# signal_proccessing.net
KiCad netlist of a schematic drawn in Altium Designer
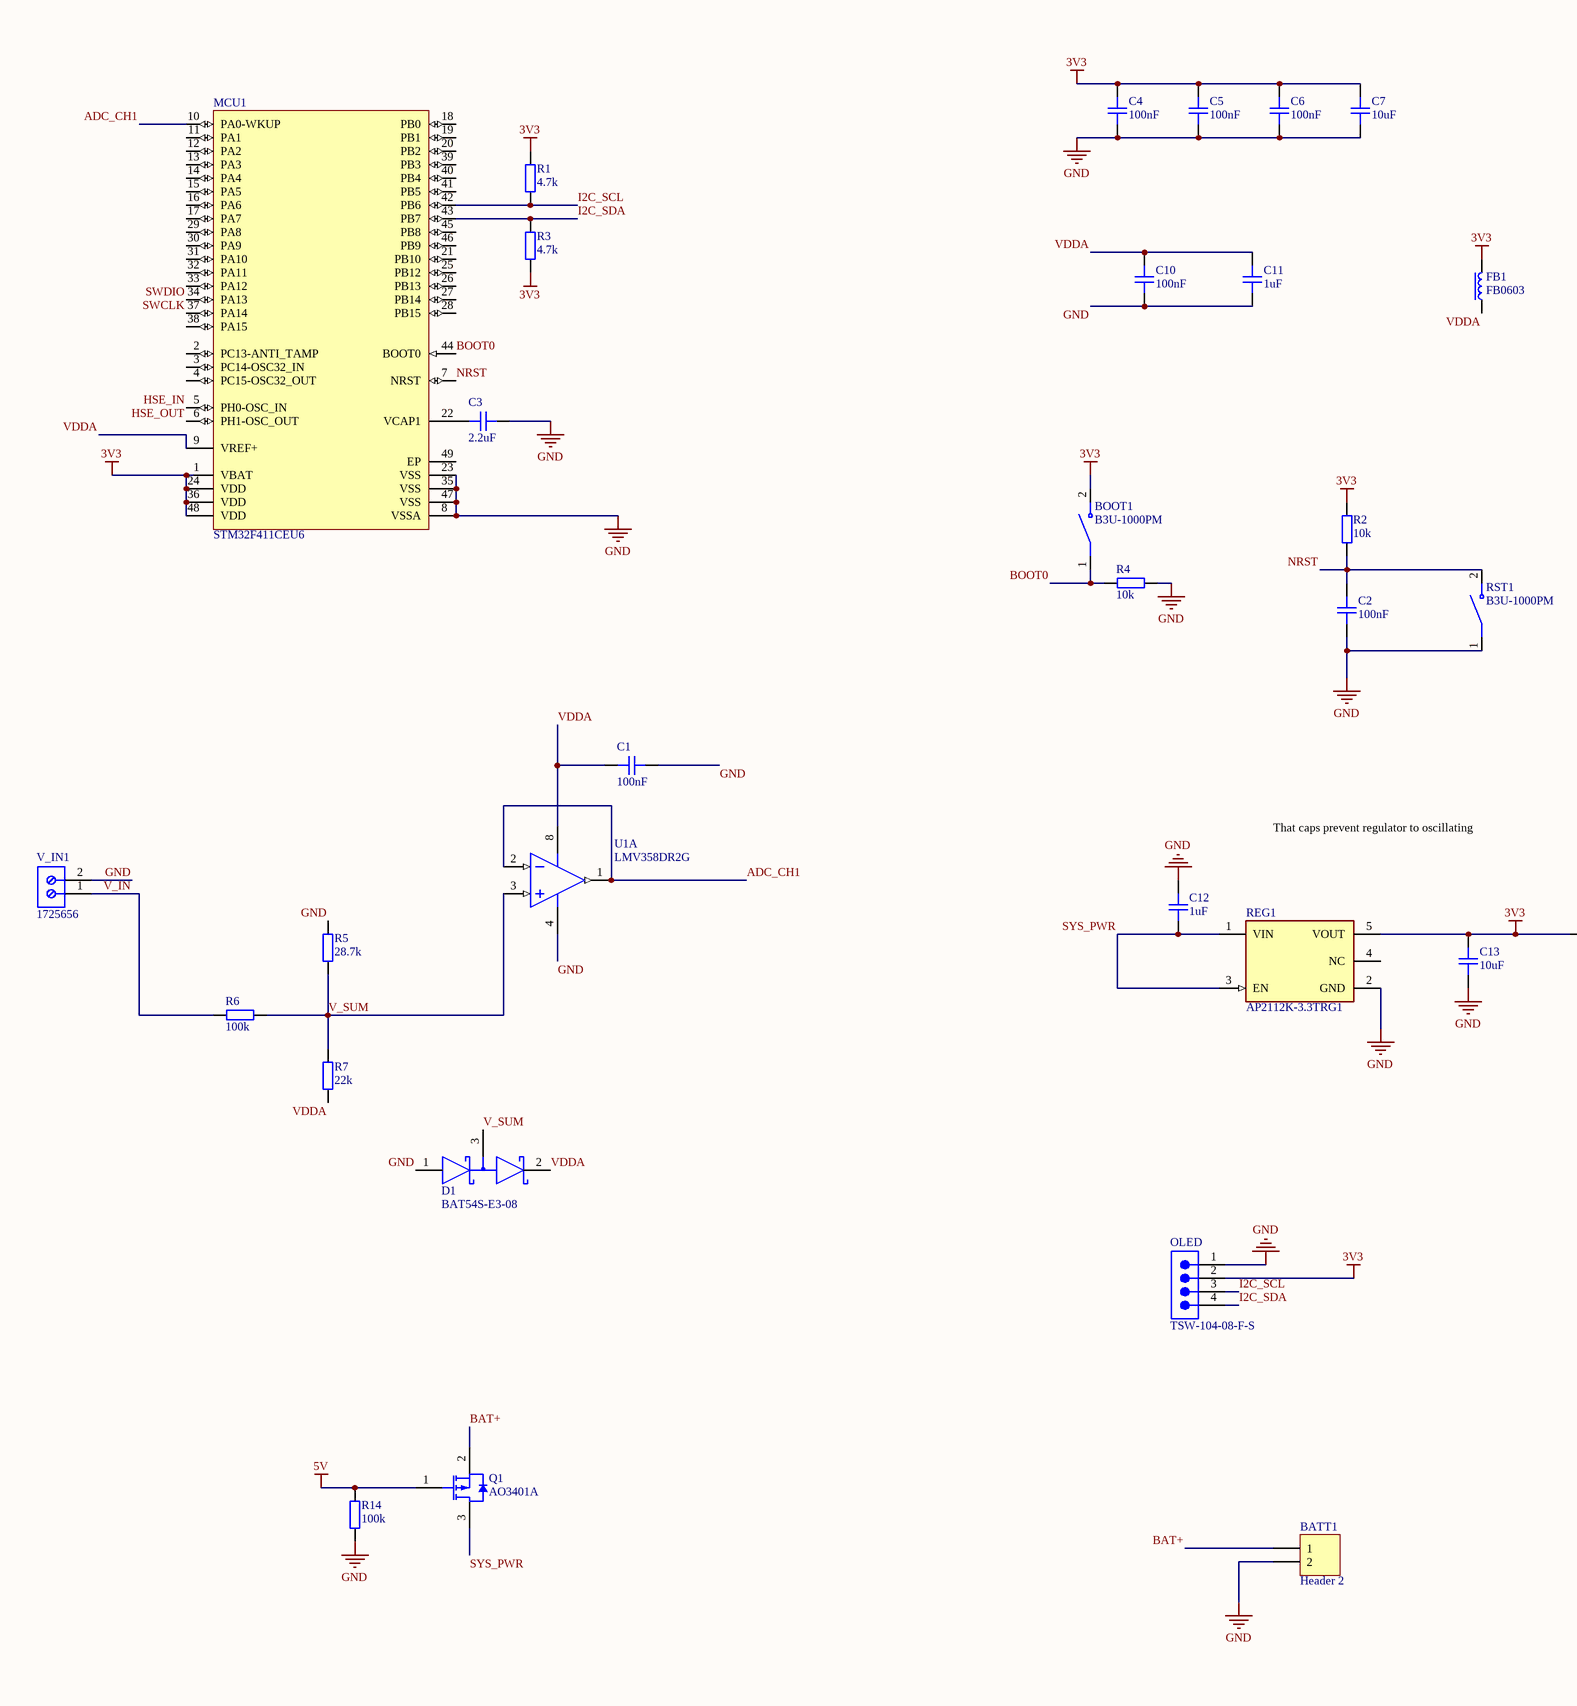
[diagram p0: signal_proccessing.SchDoc, left]
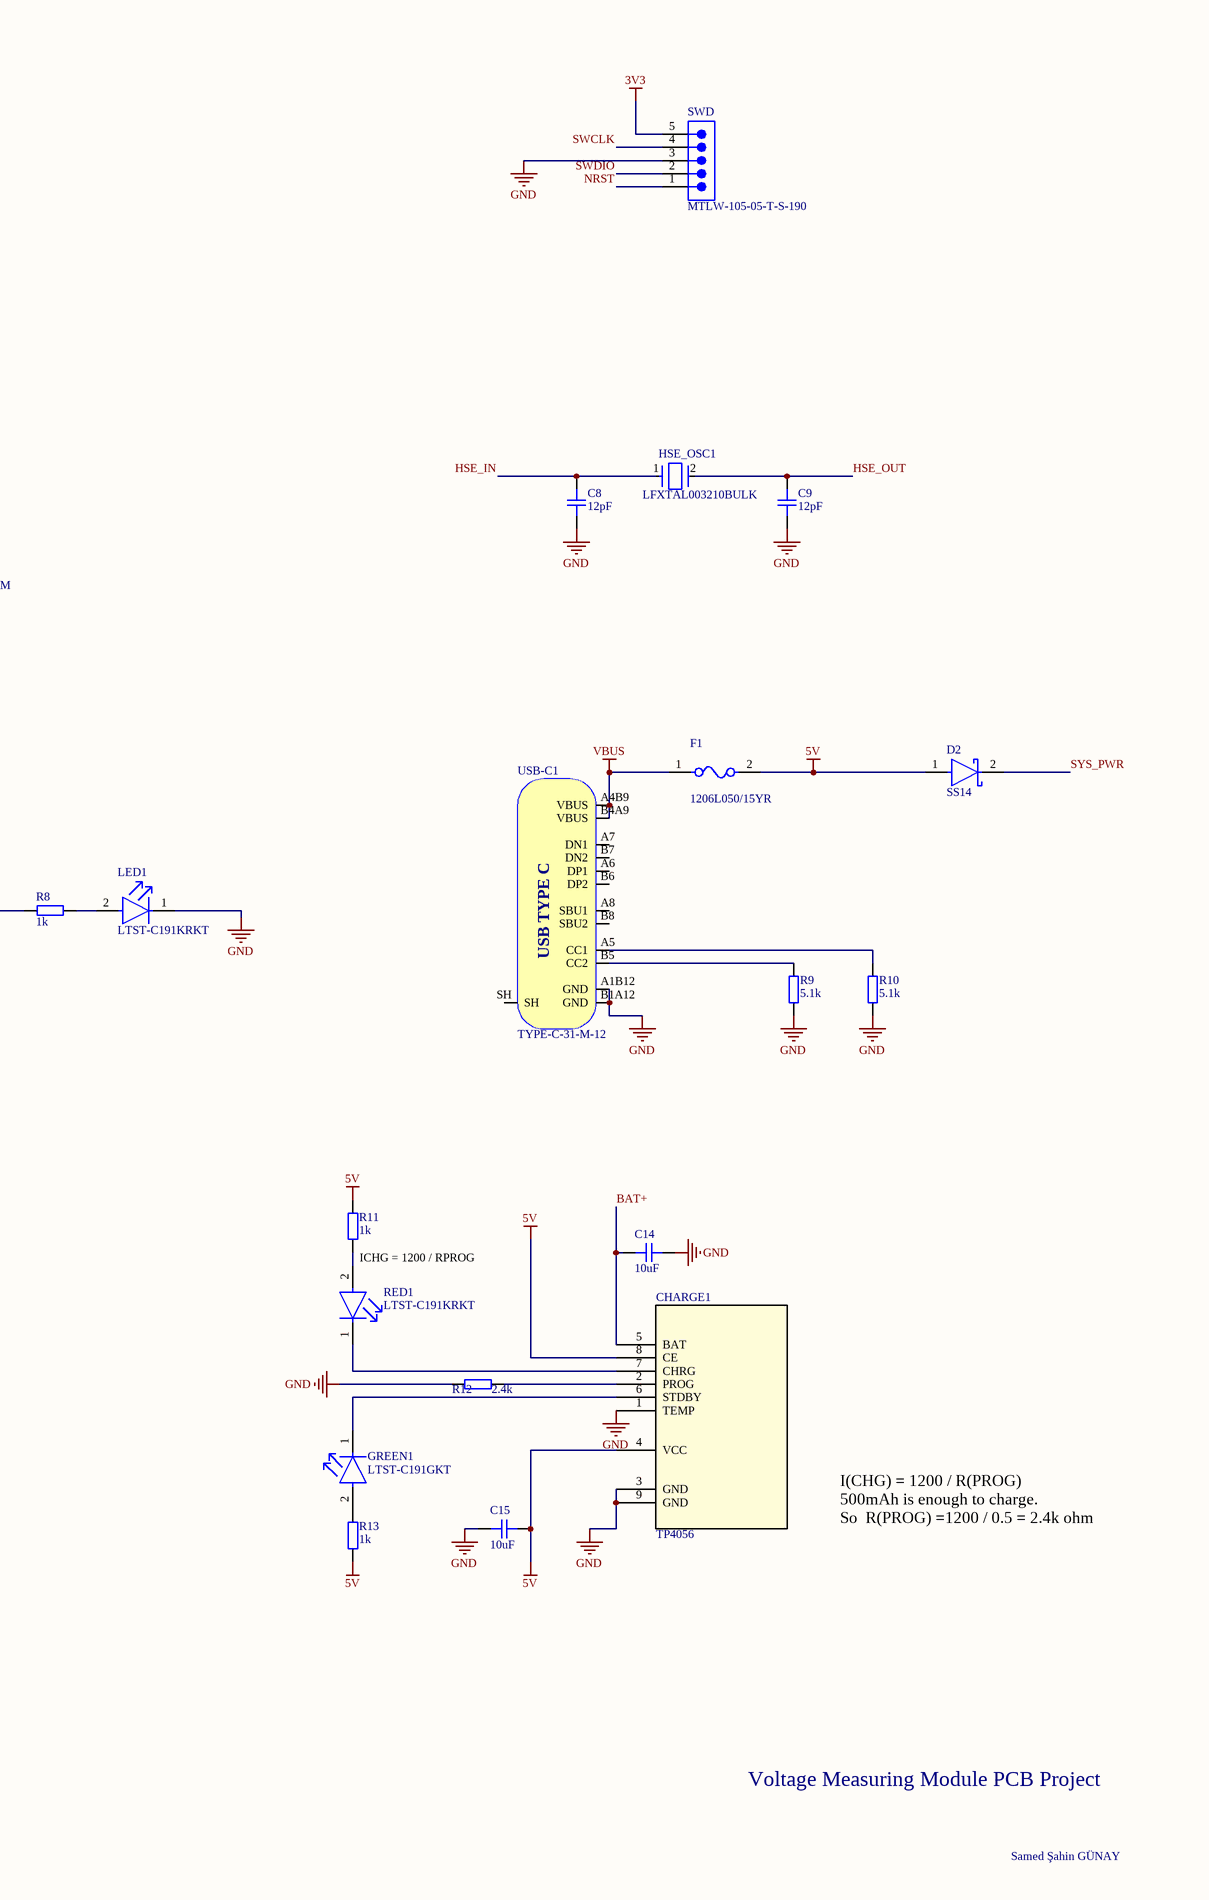
[diagram p1: signal_proccessing.SchDoc, right]

(export (version "E")
  (design (tool "Eeschema 10.0.6"))
  (components
    (comp (ref "BATT1")
      (value "Header 2")
      (footprint "HDR1X2")
      (description "Header, 2-Pin")
      (fields (field (name "PUBLISHER") "Altium Limited"))
      (libsource (lib "Miscellaneous Connectors") (part "Header 2"))
    )
    (comp (ref "BOOT1")
      (value "B3U-1000PM")
      (footprint "SW_B3U-1000PM")
      (description "Top, w/o Boss 1k Reel ¦ Omron Electronic Components B3U-1000PM")
      (fields (field (name "MF") "Omron"))
      (libsource (lib "B3U-1000PM") (part "B3U-1000PM"))
    )
    (comp (ref "C1")
      (value "100nF")
      (footprint "CAP_0402")
      (description "Capacitor SMD 0402")
      (libsource (lib "Schematic-Lib-PhilsLab") (part "CAP_0402"))
    )
    (comp (ref "C2")
      (value "100nF")
      (footprint "CAP_0402")
      (description "Capacitor SMD 0402")
      (libsource (lib "Schematic-Lib-PhilsLab") (part "CAP_0402"))
    )
    (comp (ref "C3")
      (value "2.2uF")
      (footprint "CAP_0603")
      (description "Capacitor SMD 0603")
      (libsource (lib "Schematic-Lib-PhilsLab") (part "CAP_0603"))
    )
    (comp (ref "C4")
      (value "100nF")
      (footprint "CAP_0402")
      (description "Capacitor SMD 0402")
      (libsource (lib "Schematic-Lib-PhilsLab") (part "CAP_0402"))
    )
    (comp (ref "C5")
      (value "100nF")
      (footprint "CAP_0402")
      (description "Capacitor SMD 0402")
      (libsource (lib "Schematic-Lib-PhilsLab") (part "CAP_0402"))
    )
    (comp (ref "C6")
      (value "100nF")
      (footprint "CAP_0402")
      (description "Capacitor SMD 0402")
      (libsource (lib "Schematic-Lib-PhilsLab") (part "CAP_0402"))
    )
    (comp (ref "C7")
      (value "10uF")
      (footprint "CAP_0603")
      (description "Capacitor SMD 0603")
      (libsource (lib "Schematic-Lib-PhilsLab") (part "CAP_0603"))
    )
    (comp (ref "C8")
      (value "12pF")
      (footprint "CAP_0402")
      (description "Capacitor SMD 0402")
      (libsource (lib "Schematic-Lib-PhilsLab") (part "CAP_0402"))
    )
    (comp (ref "C9")
      (value "12pF")
      (footprint "CAP_0402")
      (description "Capacitor SMD 0402")
      (libsource (lib "Schematic-Lib-PhilsLab") (part "CAP_0402"))
    )
    (comp (ref "C10")
      (value "100nF")
      (footprint "CAP_0402")
      (description "Capacitor SMD 0402")
      (libsource (lib "Schematic-Lib-PhilsLab") (part "CAP_0402"))
    )
    (comp (ref "C11")
      (value "1uF")
      (footprint "CAP_0603")
      (description "Capacitor SMD 0603")
      (libsource (lib "Schematic-Lib-PhilsLab") (part "CAP_0603"))
    )
    (comp (ref "C12")
      (value "1uF")
      (footprint "CAP_0603")
      (description "Capacitor SMD 0603")
      (libsource (lib "Schematic-Lib-PhilsLab") (part "CAP_0603"))
    )
    (comp (ref "C13")
      (value "10uF")
      (footprint "CAP_0603")
      (description "Capacitor SMD 0603")
      (libsource (lib "Schematic-Lib-PhilsLab") (part "CAP_0603"))
    )
    (comp (ref "C14")
      (value "10uF")
      (footprint "CAP_0603")
      (description "Capacitor SMD 0603")
      (libsource (lib "Schematic-Lib-PhilsLab") (part "CAP_0603"))
    )
    (comp (ref "C15")
      (value "10uF")
      (footprint "CAP_0603")
      (description "Capacitor SMD 0603")
      (libsource (lib "Schematic-Lib-PhilsLab") (part "CAP_0603"))
    )
    (comp (ref "CHARGE1")
      (value "TP4056")
      (footprint "ESOP8_UMW")
      (description "Description")
      (fields (field (name "COPYRIGHT") "Copyright (C) 2025 Ultra Librarian. All rights reserved."))
      (libsource (lib "TP4056") (part "TP4056"))
    )
    (comp (ref "D1")
      (value "BAT54S-E3-08")
      (footprint "FP-6_541-5014_01-4-MFG")
      (description "DIODE ARRAY SCHOTTKY 30V SOT23")
      (fields
        (field (name "OCTOPART") "https://octopart.com/bat54s-e3-08-vishay-29186616")
        (field (name "MANUFACTURER") "Vishay")
      )
      (libsource (lib "Altium Content Vault") (part "826853e049917e74922d2434823b145"))
    )
    (comp (ref "D2")
      (value "SS14")
      (footprint "FP-403AE-MFG")
      (description "DIODE SCHOTTKY 40V 1A SMA")
      (fields
        (field (name "MANUFACTURER") "ON Semiconductor")
        (field (name "OCTOPART") "https://octopart.com/ss14-on+semiconductor-29205033")
      )
      (libsource (lib "Altium Content Vault") (part "360ad2f4ac25a952324d13796385471"))
    )
    (comp (ref "F1")
      (value "1206L050/15YR")
      (footprint "FP-1206L-MFG")
      (description "PTC RESET FUSE 15V 500MA 1206")
      (fields
        (field (name "MANUFACTURER") "Littelfuse Inc")
        (field (name "OCTOPART") "https://octopart.com/1206l050%2F15yr-littelfuse-673645")
      )
      (libsource (lib "Altium Content Vault") (part "5bcf9b9f640e542cf0359d10258e979"))
    )
    (comp (ref "FB1")
      (value "FB0603")
      (footprint "FB_0603")
      (description "Ferrite Bead SMD 0603")
      (libsource (lib "Schematic-Lib-PhilsLab") (part "FB_0603"))
    )
    (comp (ref "GREEN1")
      (value "LTST-C191GKT")
      (footprint "FP-LTST-C191GKT-MFG")
      (description "LED GREEN CLEAR CHIP SMD")
      (libsource (lib "Altium Content Vault") (part "8706943c75ba83719d021d2fdc84c58"))
    )
    (comp (ref "HSE_OSC1")
      (value "LFXTAL003210BULK")
      (footprint "FP-LFXTAL003210BULK-MFG")
      (description "CRYSTAL 12.0MHZ 16PF SMD")
      (fields
        (field (name "MANUFACTURER") "IQD Frequency Products")
        (field (name "OCTOPART") "https://octopart.com/lfxtal003210bulk-iqd+frequency+products-20904063")
      )
      (libsource (lib "Altium Content Vault") (part "c23a69dc6c9e2f18f2079038eb95dd1"))
    )
    (comp (ref "LED1")
      (value "LTST-C191KRKT")
      (footprint "FP-LTST-C191KRKT-MFG")
      (fields (field (name "VOLTAGE") "2V"))
      (libsource (lib "Altium Content Vault") (part "8706943c75ba83719d021d2fdc84c58"))
    )
    (comp (ref "MCU1")
      (value "STM32F411CEU6")
      (footprint "STM-UFQFPN48_L")
      (libsource (lib "Altium Content Vault") (part "MC-ARM-STM32F411-UFQFPN48"))
    )
    (comp (ref "OLED")
      (value "TSW-104-08-F-S")
      (footprint "SMTC-TSW-104-08-X-S")
      (description "0.025\" SQ Post Header, Through-hole, Vertical, -55 to 125 degC, 2.54 mm Pitch, 4-Pin, Male, RoHS")
      (fields (field (name "MANUFACTURER") "Samtec"))
      (libsource (lib "Altium Content Vault") (part "SMTC-TSW-104-08-X-S"))
    )
    (comp (ref "Q1")
      (value "AO3401A")
      (footprint "AO-SOT-23-3L_V")
      (description "P-Channel MOSFET, 30 V, 4 A, -55 to 150 degC, 3-Pin SOT-23-3L, RoHS, Tape and Reel")
      (fields (field (name "MANUFACTURER") "Alpha and Omega"))
      (libsource (lib "Altium Content Vault") (part "PEMOS-GSD-3"))
    )
    (comp (ref "R1")
      (value "4.7k")
      (footprint "RES_0603")
      (description "Resistor SMD 0603")
      (libsource (lib "Schematic-Lib-PhilsLab") (part "RES_0603"))
    )
    (comp (ref "R2")
      (value "10k")
      (footprint "RES_0603")
      (description "Resistor SMD 0603")
      (libsource (lib "Schematic-Lib-PhilsLab") (part "RES_0603"))
    )
    (comp (ref "R3")
      (value "4.7k")
      (footprint "RES_0603")
      (description "Resistor SMD 0603")
      (libsource (lib "Schematic-Lib-PhilsLab") (part "RES_0603"))
    )
    (comp (ref "R4")
      (value "10k")
      (footprint "RES_0603")
      (description "Resistor SMD 0603")
      (libsource (lib "Schematic-Lib-PhilsLab") (part "RES_0603"))
    )
    (comp (ref "R5")
      (value "28.7k")
      (footprint "RES_0603")
      (description "Resistor SMD 0603")
      (libsource (lib "Schematic-Lib-PhilsLab") (part "RES_0603"))
    )
    (comp (ref "R6")
      (value "100k")
      (footprint "RES_0603")
      (description "Resistor SMD 0603")
      (libsource (lib "Schematic-Lib-PhilsLab") (part "RES_0603"))
    )
    (comp (ref "R7")
      (value "22k")
      (footprint "RES_0603")
      (description "Resistor SMD 0603")
      (libsource (lib "Schematic-Lib-PhilsLab") (part "RES_0603"))
    )
    (comp (ref "R8")
      (value "1k")
      (footprint "RES_0603")
      (description "Resistor SMD 0603")
      (libsource (lib "Schematic-Lib-PhilsLab") (part "RES_0603"))
    )
    (comp (ref "R9")
      (value "5.1k")
      (footprint "RES_0603")
      (description "Resistor SMD 0603")
      (libsource (lib "Schematic-Lib-PhilsLab") (part "RES_0603"))
    )
    (comp (ref "R10")
      (value "5.1k")
      (footprint "RES_0603")
      (description "Resistor SMD 0603")
      (libsource (lib "Schematic-Lib-PhilsLab") (part "RES_0603"))
    )
    (comp (ref "R11")
      (value "1k")
      (footprint "RES_0603")
      (description "Resistor SMD 0603")
      (libsource (lib "Schematic-Lib-PhilsLab") (part "RES_0603"))
    )
    (comp (ref "R12")
      (value "2.4k")
      (footprint "RES_0603")
      (description "Resistor SMD 0603")
      (libsource (lib "Schematic-Lib-PhilsLab") (part "RES_0603"))
    )
    (comp (ref "R13")
      (value "1k")
      (footprint "RES_0603")
      (description "Resistor SMD 0603")
      (libsource (lib "Schematic-Lib-PhilsLab") (part "RES_0603"))
    )
    (comp (ref "R14")
      (value "100k")
      (footprint "RES_0603")
      (description "Resistor SMD 0603")
      (libsource (lib "Schematic-Lib-PhilsLab") (part "RES_0603"))
    )
    (comp (ref "RED1")
      (value "LTST-C191KRKT")
      (footprint "FP-LTST-C191KRKT-MFG")
      (fields (field (name "VOLTAGE") "2V"))
      (libsource (lib "Altium Content Vault") (part "8706943c75ba83719d021d2fdc84c58"))
    )
    (comp (ref "REG1")
      (value "AP2112K-3.3TRG1")
      (footprint "FP-SOT25-IPC_A")
      (description "IC REG LINEAR 3.3V 600MA SOT25")
      (libsource (lib "Altium Content Vault") (part "c8ab751aee5229183125ab046a11caa"))
    )
    (comp (ref "RST1")
      (value "B3U-1000PM")
      (footprint "SW_B3U-1000PM")
      (description "Top, w/o Boss 1k Reel ¦ Omron Electronic Components B3U-1000PM")
      (fields (field (name "MF") "Omron"))
      (libsource (lib "B3U-1000PM") (part "B3U-1000PM"))
    )
    (comp (ref "SWD")
      (value "MTLW-105-05-T-S-190")
      (footprint "SMTC-MTLW-105-05-X-S-190")
      (fields (field (name "MANUFACTURER") "Samtec"))
      (libsource (lib "Altium Content Vault") (part "SMTC-MTLW-105-05-X-S-190"))
    )
    (comp (ref "U1")
      (value "LMV358DR2G")
      (footprint "ONSC-SOIC-8-751-07_V")
      (fields (field (name "MANUFACTURER") "On Semiconductor"))
      (libsource (lib "Altium Content Vault") (part "ONSC-LMV358-SOIC-8-751-07"))
    )
    (comp (ref "USB-C1")
      (value "TYPE-C-31-M-12")
      (footprint "TYPE-C-31-M-12")
      (description "USB Type C Connector Horizontal SMT")
      (fields (field (name "MANUFACTURER") "Koren Hroparts"))
      (libsource (lib "Schematic-Lib-PhilsLab") (part "TYPE-C-31-M-12"))
    )
    (comp (ref "V_IN1")
      (value "1725656")
      (footprint "PHOE-1725656-2")
      (description "Male Header, Pitch 2.54 mm, 1 x 2 Position, Height 9 mm, Tail Length 3.5 mm")
      (fields (field (name "MANUFACTURER") "Phoenix Contact"))
      (libsource (lib "Altium Content Vault") (part "CN-1P-F-TB2"))
    )
  )
  (nets
    (net (code "1") (name "/ADC_CH1") (class "Default")
      (node (ref "MCU1") (pin "10") (pinfunction "PA0-WKUP_10") (pintype "bidirectional"))
      (node (ref "U1") (pin "1") (pinfunction "OUTA_1") (pintype "output"))
      (node (ref "U1") (pin "2") (pinfunction "INA-_2") (pintype "input"))
    )
    (net (code "2") (name "/BAT+") (class "Default")
      (node (ref "BATT1") (pin "1") (pinfunction "1_1") (pintype "passive"))
      (node (ref "C14") (pin "1") (pinfunction "1_1") (pintype "passive"))
      (node (ref "CHARGE1") (pin "5") (pinfunction "BAT_5") (pintype "passive"))
      (node (ref "Q1") (pin "2") (pinfunction "SOURCE_2") (pintype "passive"))
    )
    (net (code "3") (name "/BOOT0") (class "Default")
      (node (ref "BOOT1") (pin "1") (pinfunction "1_1") (pintype "passive"))
      (node (ref "MCU1") (pin "44") (pinfunction "BOOT0_44") (pintype "input"))
      (node (ref "R4") (pin "1") (pinfunction "1_1") (pintype "passive"))
    )
    (net (code "4") (name "/HSE_IN") (class "Default")
      (node (ref "C8") (pin "2") (pinfunction "2_2") (pintype "passive"))
      (node (ref "HSE_OSC1") (pin "1") (pinfunction "1_1") (pintype "passive"))
      (node (ref "MCU1") (pin "5") (pinfunction "PH0-OSC_IN_5") (pintype "bidirectional"))
    )
    (net (code "5") (name "/HSE_OUT") (class "Default")
      (node (ref "C9") (pin "2") (pinfunction "2_2") (pintype "passive"))
      (node (ref "HSE_OSC1") (pin "2") (pinfunction "2_2") (pintype "passive"))
      (node (ref "MCU1") (pin "6") (pinfunction "PH1-OSC_OUT_6") (pintype "bidirectional"))
    )
    (net (code "6") (name "/I2C_SCL") (class "Default")
      (node (ref "MCU1") (pin "42") (pinfunction "PB6_42") (pintype "bidirectional"))
      (node (ref "OLED") (pin "3") (pinfunction "3_3") (pintype "passive"))
      (node (ref "R1") (pin "1") (pinfunction "1_1") (pintype "passive"))
    )
    (net (code "7") (name "/I2C_SDA") (class "Default")
      (node (ref "MCU1") (pin "43") (pinfunction "PB7_43") (pintype "bidirectional"))
      (node (ref "OLED") (pin "4") (pinfunction "4_4") (pintype "passive"))
      (node (ref "R3") (pin "2") (pinfunction "2_2") (pintype "passive"))
    )
    (net (code "8") (name "/NRST") (class "Default")
      (node (ref "C2") (pin "2") (pinfunction "2_2") (pintype "passive"))
      (node (ref "MCU1") (pin "7") (pinfunction "NRST_7") (pintype "bidirectional"))
      (node (ref "R2") (pin "1") (pinfunction "1_1") (pintype "passive"))
      (node (ref "RST1") (pin "2") (pinfunction "2_2") (pintype "passive"))
      (node (ref "SWD") (pin "1") (pinfunction "1_1") (pintype "passive"))
    )
    (net (code "9") (name "/SWCLK") (class "Default")
      (node (ref "MCU1") (pin "37") (pinfunction "PA14_37") (pintype "bidirectional"))
      (node (ref "SWD") (pin "4") (pinfunction "4_4") (pintype "passive"))
    )
    (net (code "10") (name "/SWDIO") (class "Default")
      (node (ref "MCU1") (pin "34") (pinfunction "PA13_34") (pintype "bidirectional"))
      (node (ref "SWD") (pin "2") (pinfunction "2_2") (pintype "passive"))
    )
    (net (code "11") (name "/SYS_PWR") (class "Default")
      (node (ref "C12") (pin "1") (pinfunction "1_1") (pintype "passive"))
      (node (ref "D2") (pin "2") (pinfunction "C_2") (pintype "passive"))
      (node (ref "Q1") (pin "3") (pinfunction "DRAIN_3") (pintype "passive"))
      (node (ref "REG1") (pin "1") (pinfunction "VIN_1") (pintype "power_in"))
      (node (ref "REG1") (pin "3") (pinfunction "EN_3") (pintype "input"))
    )
    (net (code "12") (name "/VDDA") (class "Default")
      (node (ref "C1") (pin "2") (pinfunction "2_2") (pintype "passive"))
      (node (ref "C10") (pin "2") (pinfunction "2_2") (pintype "passive"))
      (node (ref "C11") (pin "2") (pinfunction "2_2") (pintype "passive"))
      (node (ref "D1") (pin "2") (pinfunction "2_2") (pintype "passive"))
      (node (ref "FB1") (pin "1") (pinfunction "1_1") (pintype "passive"))
      (node (ref "MCU1") (pin "9") (pinfunction "VREF+_9") (pintype "power_in"))
      (node (ref "R7") (pin "2") (pinfunction "2_2") (pintype "passive"))
      (node (ref "U1") (pin "8") (pinfunction "V+_8") (pintype "power_in"))
    )
    (net (code "13") (name "/V_IN") (class "Default")
      (node (ref "R6") (pin "2") (pinfunction "2_2") (pintype "passive"))
      (node (ref "V_IN1") (pin "1") (pinfunction "1_1") (pintype "passive"))
    )
    (net (code "14") (name "/V_SUM") (class "Default")
      (node (ref "D1") (pin "3") (pinfunction "3_3") (pintype "passive"))
      (node (ref "R5") (pin "2") (pinfunction "2_2") (pintype "passive"))
      (node (ref "R6") (pin "1") (pinfunction "1_1") (pintype "passive"))
      (node (ref "R7") (pin "1") (pinfunction "1_1") (pintype "passive"))
      (node (ref "U1") (pin "3") (pinfunction "INA+_3") (pintype "input"))
    )
    (net (code "15") (name "3V3") (class "Default")
      (node (ref "BOOT1") (pin "2") (pinfunction "2_2") (pintype "passive"))
      (node (ref "C13") (pin "2") (pinfunction "2_2") (pintype "passive"))
      (node (ref "C4") (pin "2") (pinfunction "2_2") (pintype "passive"))
      (node (ref "C5") (pin "2") (pinfunction "2_2") (pintype "passive"))
      (node (ref "C6") (pin "2") (pinfunction "2_2") (pintype "passive"))
      (node (ref "C7") (pin "2") (pinfunction "2_2") (pintype "passive"))
      (node (ref "FB1") (pin "2") (pinfunction "2_2") (pintype "passive"))
      (node (ref "MCU1") (pin "1") (pinfunction "VBAT_1") (pintype "power_in"))
      (node (ref "MCU1") (pin "24") (pinfunction "VDD_24") (pintype "power_in"))
      (node (ref "MCU1") (pin "36") (pinfunction "VDD_36") (pintype "power_in"))
      (node (ref "MCU1") (pin "48") (pinfunction "VDD_48") (pintype "power_in"))
      (node (ref "OLED") (pin "2") (pinfunction "2_2") (pintype "passive"))
      (node (ref "R1") (pin "2") (pinfunction "2_2") (pintype "passive"))
      (node (ref "R2") (pin "2") (pinfunction "2_2") (pintype "passive"))
      (node (ref "R3") (pin "1") (pinfunction "1_1") (pintype "passive"))
      (node (ref "R8") (pin "1") (pinfunction "1_1") (pintype "passive"))
      (node (ref "REG1") (pin "5") (pinfunction "VOUT_5") (pintype "power_in"))
      (node (ref "SWD") (pin "5") (pinfunction "5_5") (pintype "passive"))
    )
    (net (code "16") (name "5V") (class "Default")
      (node (ref "C15") (pin "2") (pinfunction "2_2") (pintype "passive"))
      (node (ref "CHARGE1") (pin "4") (pinfunction "VCC_4") (pintype "power_in"))
      (node (ref "CHARGE1") (pin "8") (pinfunction "CE_8") (pintype "passive"))
      (node (ref "D2") (pin "1") (pinfunction "A_1") (pintype "passive"))
      (node (ref "F1") (pin "2") (pinfunction "2_2") (pintype "passive"))
      (node (ref "Q1") (pin "1") (pinfunction "GATE_1") (pintype "passive"))
      (node (ref "R11") (pin "1") (pinfunction "1_1") (pintype "passive"))
      (node (ref "R13") (pin "2") (pinfunction "2_2") (pintype "passive"))
      (node (ref "R14") (pin "1") (pinfunction "1_1") (pintype "passive"))
    )
    (net (code "17") (name "GND") (class "Default")
      (node (ref "BATT1") (pin "2") (pinfunction "2_2") (pintype "passive"))
      (node (ref "C1") (pin "1") (pinfunction "1_1") (pintype "passive"))
      (node (ref "C10") (pin "1") (pinfunction "1_1") (pintype "passive"))
      (node (ref "C11") (pin "1") (pinfunction "1_1") (pintype "passive"))
      (node (ref "C12") (pin "2") (pinfunction "2_2") (pintype "passive"))
      (node (ref "C13") (pin "1") (pinfunction "1_1") (pintype "passive"))
      (node (ref "C14") (pin "2") (pinfunction "2_2") (pintype "passive"))
      (node (ref "C15") (pin "1") (pinfunction "1_1") (pintype "passive"))
      (node (ref "C2") (pin "1") (pinfunction "1_1") (pintype "passive"))
      (node (ref "C3") (pin "1") (pinfunction "1_1") (pintype "passive"))
      (node (ref "C4") (pin "1") (pinfunction "1_1") (pintype "passive"))
      (node (ref "C5") (pin "1") (pinfunction "1_1") (pintype "passive"))
      (node (ref "C6") (pin "1") (pinfunction "1_1") (pintype "passive"))
      (node (ref "C7") (pin "1") (pinfunction "1_1") (pintype "passive"))
      (node (ref "C8") (pin "1") (pinfunction "1_1") (pintype "passive"))
      (node (ref "C9") (pin "1") (pinfunction "1_1") (pintype "passive"))
      (node (ref "CHARGE1") (pin "1") (pinfunction "TEMP_1") (pintype "passive"))
      (node (ref "CHARGE1") (pin "3") (pinfunction "GND_3") (pintype "power_in"))
      (node (ref "CHARGE1") (pin "9") (pinfunction "GND_9") (pintype "power_in"))
      (node (ref "D1") (pin "1") (pinfunction "1_1") (pintype "passive"))
      (node (ref "LED1") (pin "1") (pinfunction "C_1") (pintype "passive"))
      (node (ref "MCU1") (pin "23") (pinfunction "VSS_23") (pintype "power_in"))
      (node (ref "MCU1") (pin "35") (pinfunction "VSS_35") (pintype "power_in"))
      (node (ref "MCU1") (pin "47") (pinfunction "VSS_47") (pintype "power_in"))
      (node (ref "MCU1") (pin "8") (pinfunction "VSSA_8") (pintype "power_in"))
      (node (ref "OLED") (pin "1") (pinfunction "1_1") (pintype "passive"))
      (node (ref "R10") (pin "2") (pinfunction "2_2") (pintype "passive"))
      (node (ref "R12") (pin "1") (pinfunction "1_1") (pintype "passive"))
      (node (ref "R14") (pin "2") (pinfunction "2_2") (pintype "passive"))
      (node (ref "R4") (pin "2") (pinfunction "2_2") (pintype "passive"))
      (node (ref "R5") (pin "1") (pinfunction "1_1") (pintype "passive"))
      (node (ref "R9") (pin "2") (pinfunction "2_2") (pintype "passive"))
      (node (ref "REG1") (pin "2") (pinfunction "GND_2") (pintype "power_in"))
      (node (ref "RST1") (pin "1") (pinfunction "1_1") (pintype "passive"))
      (node (ref "SWD") (pin "3") (pinfunction "3_3") (pintype "passive"))
      (node (ref "U1") (pin "4") (pinfunction "V-_4") (pintype "power_in"))
      (node (ref "USB-C1") (pin "A1B12") (pinfunction "GND_A1B12") (pintype "power_in"))
      (node (ref "USB-C1") (pin "B1A12") (pinfunction "GND_B1A12") (pintype "power_in"))
      (node (ref "V_IN1") (pin "2") (pinfunction "2_2") (pintype "passive"))
    )
    (net (code "18") (name "Net-(CHARGE1-CHRG)") (class "Default")
      (node (ref "CHARGE1") (pin "7") (pinfunction "CHRG_7") (pintype "passive"))
      (node (ref "RED1") (pin "1") (pinfunction "C_1") (pintype "passive"))
    )
    (net (code "19") (name "Net-(CHARGE1-PROG)") (class "Default")
      (node (ref "CHARGE1") (pin "2") (pinfunction "PROG_2") (pintype "passive"))
      (node (ref "R12") (pin "2") (pinfunction "2_2") (pintype "passive"))
    )
    (net (code "20") (name "Net-(CHARGE1-STDBY)") (class "Default")
      (node (ref "CHARGE1") (pin "6") (pinfunction "STDBY_6") (pintype "passive"))
      (node (ref "GREEN1") (pin "1") (pinfunction "C_1") (pintype "passive"))
    )
    (net (code "21") (name "Net-(GREEN1-A)") (class "Default")
      (node (ref "GREEN1") (pin "2") (pinfunction "A_2") (pintype "passive"))
      (node (ref "R13") (pin "1") (pinfunction "1_1") (pintype "passive"))
    )
    (net (code "22") (name "Net-(LED1-A)") (class "Default")
      (node (ref "LED1") (pin "2") (pinfunction "A_2") (pintype "passive"))
      (node (ref "R8") (pin "2") (pinfunction "2_2") (pintype "passive"))
    )
    (net (code "23") (name "Net-(MCU1-VCAP1)") (class "Default")
      (node (ref "C3") (pin "2") (pinfunction "2_2") (pintype "passive"))
      (node (ref "MCU1") (pin "22") (pinfunction "VCAP1_22") (pintype "passive"))
    )
    (net (code "24") (name "Net-(RED1-A)") (class "Default")
      (node (ref "R11") (pin "2") (pinfunction "2_2") (pintype "passive"))
      (node (ref "RED1") (pin "2") (pinfunction "A_2") (pintype "passive"))
    )
    (net (code "25") (name "Net-(USB-C1-CC1)") (class "Default")
      (node (ref "R10") (pin "1") (pinfunction "1_1") (pintype "passive"))
      (node (ref "USB-C1") (pin "A5") (pinfunction "CC1_A5") (pintype "passive"))
    )
    (net (code "26") (name "Net-(USB-C1-CC2)") (class "Default")
      (node (ref "R9") (pin "1") (pinfunction "1_1") (pintype "passive"))
      (node (ref "USB-C1") (pin "B5") (pinfunction "CC2_B5") (pintype "tri_state"))
    )
    (net (code "27") (name "VBUS") (class "Default")
      (node (ref "F1") (pin "1") (pinfunction "1_1") (pintype "passive"))
      (node (ref "USB-C1") (pin "A4B9") (pinfunction "VBUS_A4B9") (pintype "power_in"))
      (node (ref "USB-C1") (pin "B4A9") (pinfunction "VBUS_B4A9") (pintype "power_in"))
    )
    (net (code "28") (name "unconnected-(MCU1-EP-Pad49)") (class "Default")
      (node (ref "MCU1") (pin "49") (pinfunction "EP_49") (pintype "power_in"))
    )
    (net (code "29") (name "unconnected-(MCU1-PA1-Pad11)") (class "Default")
      (node (ref "MCU1") (pin "11") (pinfunction "PA1_11") (pintype "bidirectional"))
    )
    (net (code "30") (name "unconnected-(MCU1-PA2-Pad12)") (class "Default")
      (node (ref "MCU1") (pin "12") (pinfunction "PA2_12") (pintype "bidirectional"))
    )
    (net (code "31") (name "unconnected-(MCU1-PA3-Pad13)") (class "Default")
      (node (ref "MCU1") (pin "13") (pinfunction "PA3_13") (pintype "bidirectional"))
    )
    (net (code "32") (name "unconnected-(MCU1-PA4-Pad14)") (class "Default")
      (node (ref "MCU1") (pin "14") (pinfunction "PA4_14") (pintype "bidirectional"))
    )
    (net (code "33") (name "unconnected-(MCU1-PA5-Pad15)") (class "Default")
      (node (ref "MCU1") (pin "15") (pinfunction "PA5_15") (pintype "bidirectional"))
    )
    (net (code "34") (name "unconnected-(MCU1-PA6-Pad16)") (class "Default")
      (node (ref "MCU1") (pin "16") (pinfunction "PA6_16") (pintype "bidirectional"))
    )
    (net (code "35") (name "unconnected-(MCU1-PA7-Pad17)") (class "Default")
      (node (ref "MCU1") (pin "17") (pinfunction "PA7_17") (pintype "bidirectional"))
    )
    (net (code "36") (name "unconnected-(MCU1-PA8-Pad29)") (class "Default")
      (node (ref "MCU1") (pin "29") (pinfunction "PA8_29") (pintype "bidirectional"))
    )
    (net (code "37") (name "unconnected-(MCU1-PA9-Pad30)") (class "Default")
      (node (ref "MCU1") (pin "30") (pinfunction "PA9_30") (pintype "bidirectional"))
    )
    (net (code "38") (name "unconnected-(MCU1-PA10-Pad31)") (class "Default")
      (node (ref "MCU1") (pin "31") (pinfunction "PA10_31") (pintype "bidirectional"))
    )
    (net (code "39") (name "unconnected-(MCU1-PA11-Pad32)") (class "Default")
      (node (ref "MCU1") (pin "32") (pinfunction "PA11_32") (pintype "bidirectional"))
    )
    (net (code "40") (name "unconnected-(MCU1-PA12-Pad33)") (class "Default")
      (node (ref "MCU1") (pin "33") (pinfunction "PA12_33") (pintype "bidirectional"))
    )
    (net (code "41") (name "unconnected-(MCU1-PA15-Pad38)") (class "Default")
      (node (ref "MCU1") (pin "38") (pinfunction "PA15_38") (pintype "bidirectional"))
    )
    (net (code "42") (name "unconnected-(MCU1-PB0-Pad18)") (class "Default")
      (node (ref "MCU1") (pin "18") (pinfunction "PB0_18") (pintype "bidirectional"))
    )
    (net (code "43") (name "unconnected-(MCU1-PB1-Pad19)") (class "Default")
      (node (ref "MCU1") (pin "19") (pinfunction "PB1_19") (pintype "bidirectional"))
    )
    (net (code "44") (name "unconnected-(MCU1-PB2-Pad20)") (class "Default")
      (node (ref "MCU1") (pin "20") (pinfunction "PB2_20") (pintype "bidirectional"))
    )
    (net (code "45") (name "unconnected-(MCU1-PB3-Pad39)") (class "Default")
      (node (ref "MCU1") (pin "39") (pinfunction "PB3_39") (pintype "bidirectional"))
    )
    (net (code "46") (name "unconnected-(MCU1-PB4-Pad40)") (class "Default")
      (node (ref "MCU1") (pin "40") (pinfunction "PB4_40") (pintype "bidirectional"))
    )
    (net (code "47") (name "unconnected-(MCU1-PB5-Pad41)") (class "Default")
      (node (ref "MCU1") (pin "41") (pinfunction "PB5_41") (pintype "bidirectional"))
    )
    (net (code "48") (name "unconnected-(MCU1-PB8-Pad45)") (class "Default")
      (node (ref "MCU1") (pin "45") (pinfunction "PB8_45") (pintype "bidirectional"))
    )
    (net (code "49") (name "unconnected-(MCU1-PB9-Pad46)") (class "Default")
      (node (ref "MCU1") (pin "46") (pinfunction "PB9_46") (pintype "bidirectional"))
    )
    (net (code "50") (name "unconnected-(MCU1-PB10-Pad21)") (class "Default")
      (node (ref "MCU1") (pin "21") (pinfunction "PB10_21") (pintype "bidirectional"))
    )
    (net (code "51") (name "unconnected-(MCU1-PB12-Pad25)") (class "Default")
      (node (ref "MCU1") (pin "25") (pinfunction "PB12_25") (pintype "bidirectional"))
    )
    (net (code "52") (name "unconnected-(MCU1-PB13-Pad26)") (class "Default")
      (node (ref "MCU1") (pin "26") (pinfunction "PB13_26") (pintype "bidirectional"))
    )
    (net (code "53") (name "unconnected-(MCU1-PB14-Pad27)") (class "Default")
      (node (ref "MCU1") (pin "27") (pinfunction "PB14_27") (pintype "bidirectional"))
    )
    (net (code "54") (name "unconnected-(MCU1-PB15-Pad28)") (class "Default")
      (node (ref "MCU1") (pin "28") (pinfunction "PB15_28") (pintype "bidirectional"))
    )
    (net (code "55") (name "unconnected-(MCU1-PC13-ANTI_TAMP-Pad2)") (class "Default")
      (node (ref "MCU1") (pin "2") (pinfunction "PC13-ANTI_TAMP_2") (pintype "bidirectional"))
    )
    (net (code "56") (name "unconnected-(MCU1-PC14-OSC32_IN-Pad3)") (class "Default")
      (node (ref "MCU1") (pin "3") (pinfunction "PC14-OSC32_IN_3") (pintype "bidirectional"))
    )
    (net (code "57") (name "unconnected-(MCU1-PC15-OSC32_OUT-Pad4)") (class "Default")
      (node (ref "MCU1") (pin "4") (pinfunction "PC15-OSC32_OUT_4") (pintype "bidirectional"))
    )
    (net (code "58") (name "unconnected-(REG1-NC-Pad4)") (class "Default")
      (node (ref "REG1") (pin "4") (pinfunction "NC_4") (pintype "passive"))
    )
    (net (code "59") (name "unconnected-(USB-C1-DN1-PadA7)") (class "Default")
      (node (ref "USB-C1") (pin "A7") (pinfunction "DN1_A7") (pintype "bidirectional"))
    )
    (net (code "60") (name "unconnected-(USB-C1-DN2-PadB7)") (class "Default")
      (node (ref "USB-C1") (pin "B7") (pinfunction "DN2_B7") (pintype "bidirectional"))
    )
    (net (code "61") (name "unconnected-(USB-C1-DP1-PadA6)") (class "Default")
      (node (ref "USB-C1") (pin "A6") (pinfunction "DP1_A6") (pintype "bidirectional"))
    )
    (net (code "62") (name "unconnected-(USB-C1-DP2-PadB6)") (class "Default")
      (node (ref "USB-C1") (pin "B6") (pinfunction "DP2_B6") (pintype "bidirectional"))
    )
    (net (code "63") (name "unconnected-(USB-C1-PadSH)") (class "Default")
      (node (ref "USB-C1") (pin "SH") (pinfunction "SH_SH") (pintype "power_in"))
    )
    (net (code "64") (name "unconnected-(USB-C1-SBU1-PadA8)") (class "Default")
      (node (ref "USB-C1") (pin "A8") (pinfunction "SBU1_A8") (pintype "bidirectional"))
    )
    (net (code "65") (name "unconnected-(USB-C1-SBU2-PadB8)") (class "Default")
      (node (ref "USB-C1") (pin "B8") (pinfunction "SBU2_B8") (pintype "bidirectional"))
    )
  )
)
